# Sht2-V12P0_reg.net
KiCad netlist of a schematic drawn in Altium Designer
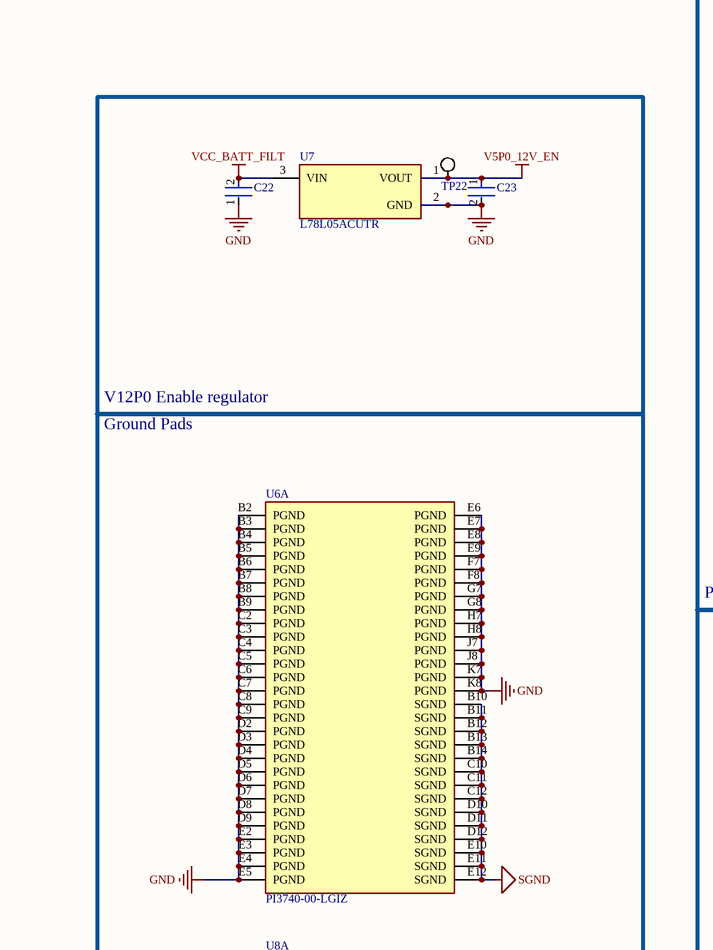
[diagram p0: Sht2-V12P0_reg.SchDoc, top left]
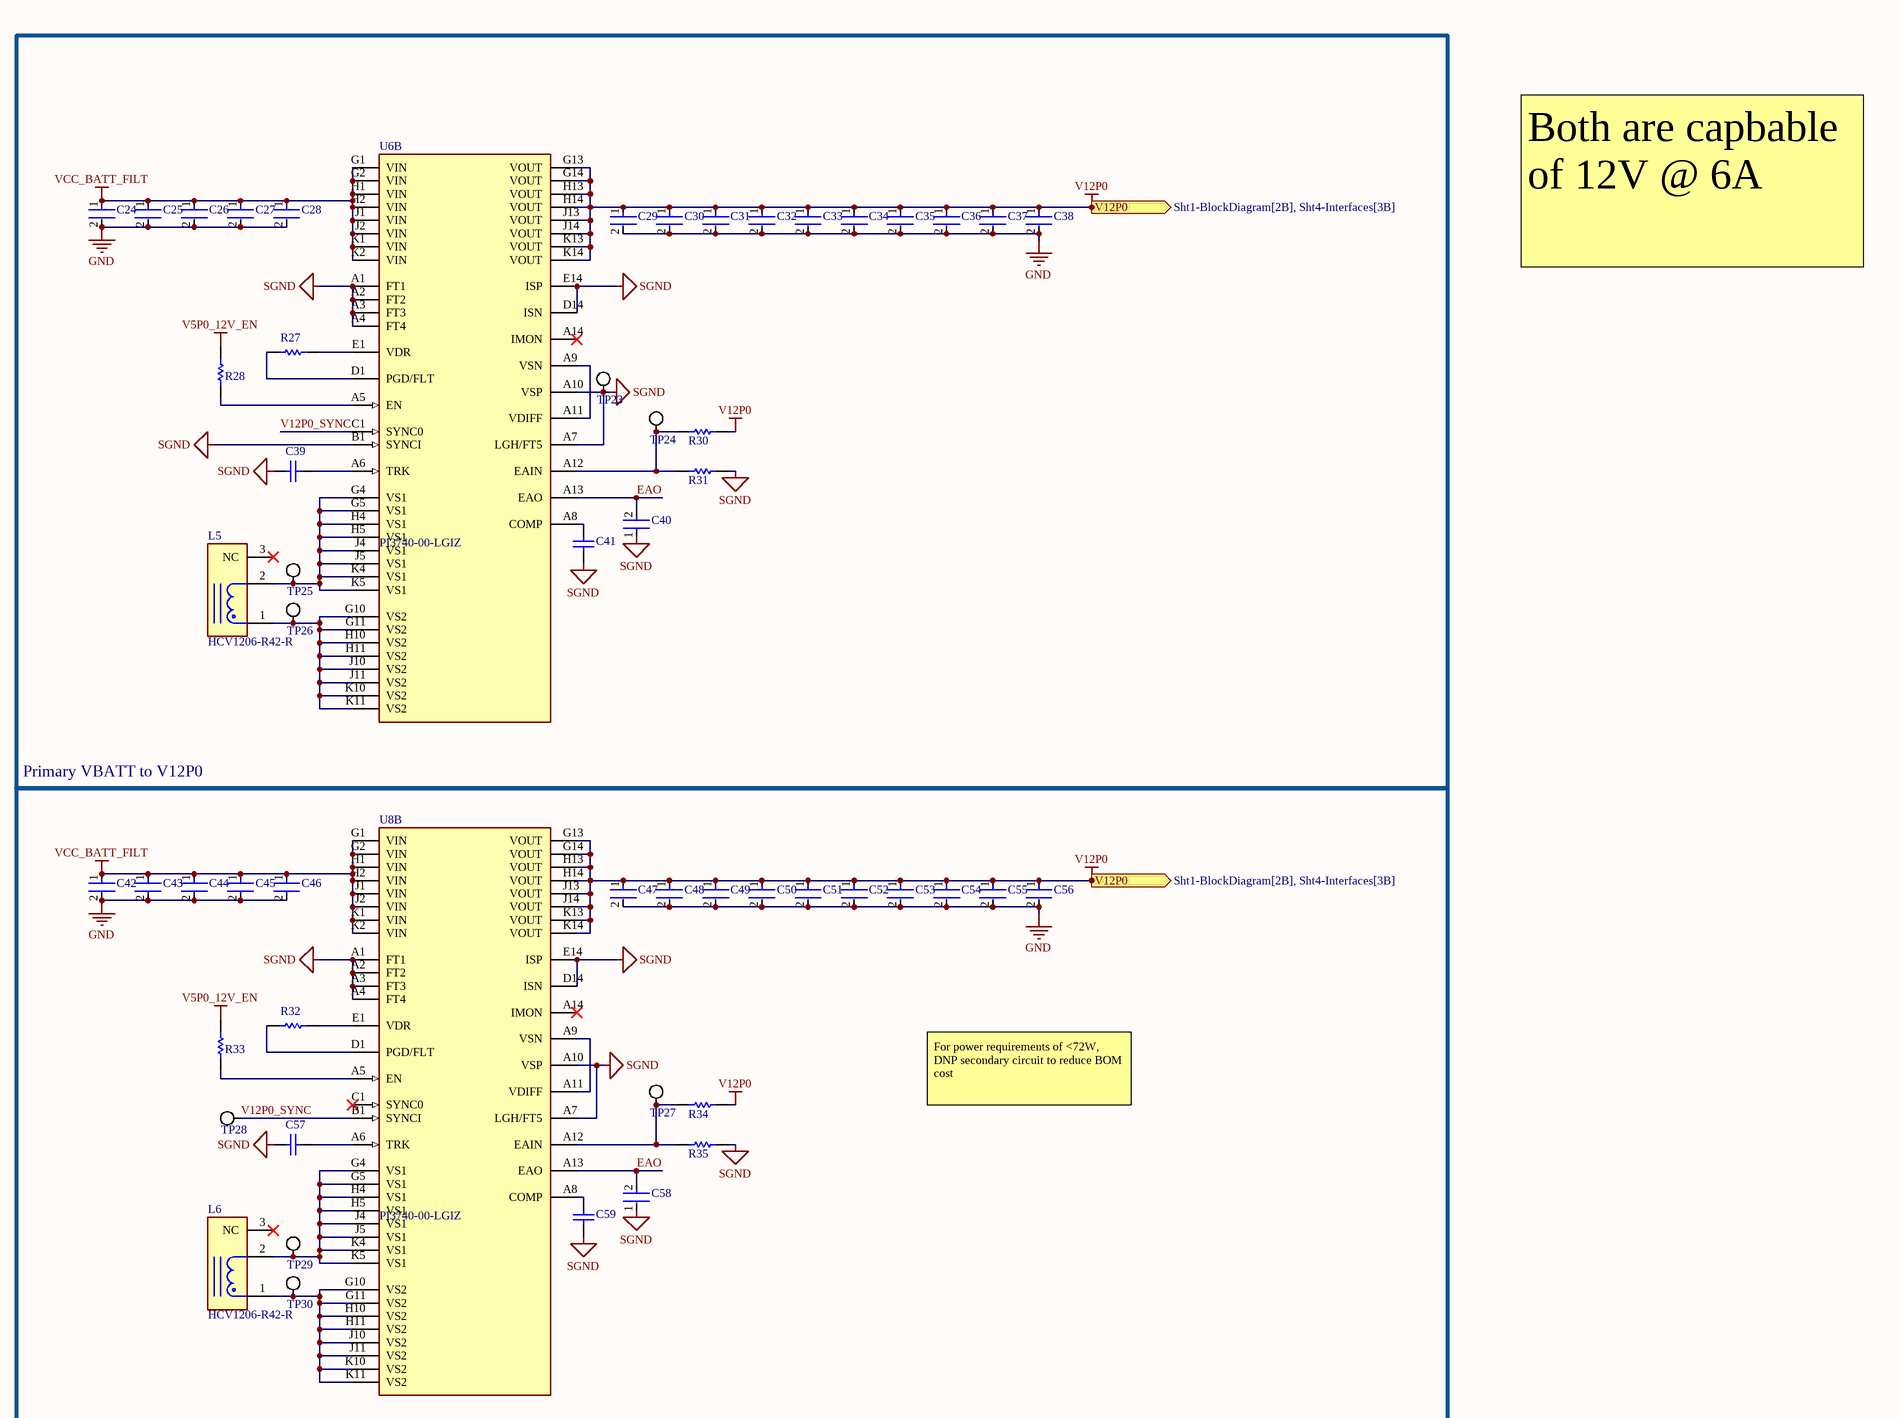
[diagram p1: Sht2-V12P0_reg.SchDoc, top right]
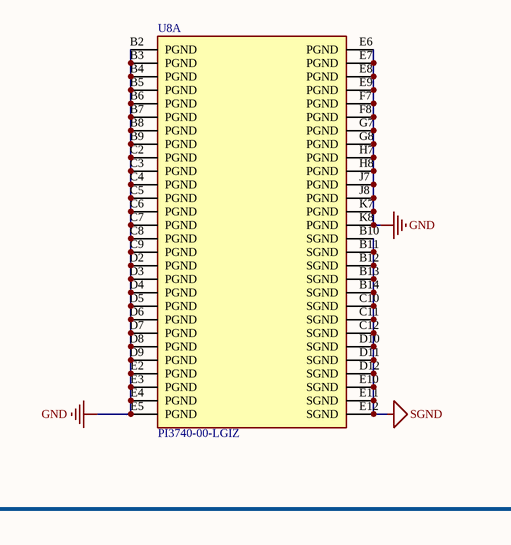
[diagram p2: Sht2-V12P0_reg.SchDoc, bottom left]
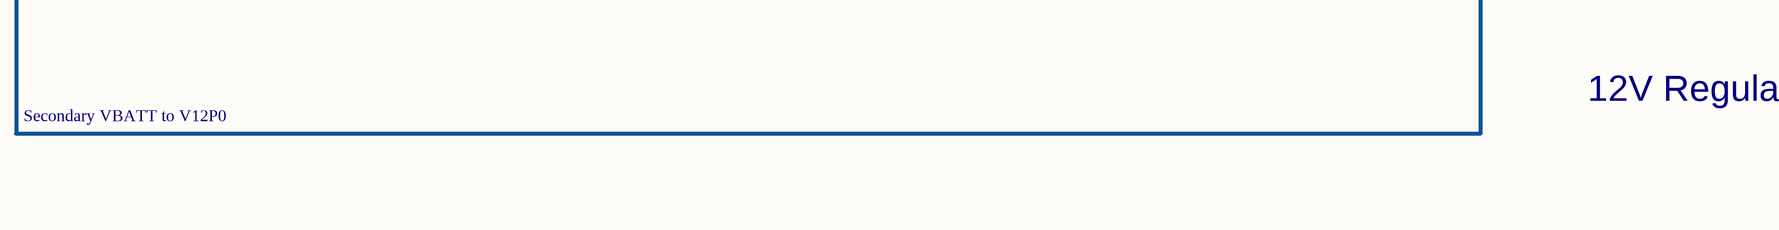
[diagram p3: Sht2-V12P0_reg.SchDoc, bottom right]

(export (version "E")
  (design (tool "Eeschema 10.0.6"))
  (components
    (comp (ref "C22")
      (value "C1608X7R1H334K080AC")
      (footprint "FP-C1608-080-0_1-IPC_A")
      (description "Multilayer Ceramic Capacitors 330nF ±10% 50V X7R SMD 0603")
      (fields (field (name "TOLERANCE") "10%") (field (name "VOLTAGE") "50V"))
      (libsource (lib "Altium Content Vault") (part "236180d848d6139a670b325ea6854c9"))
    )
    (comp (ref "C23")
      (value "CGA3E2X7R1H104K080AA")
      (footprint "FP-CGA3E-0_3-0_1-IPC_A")
      (description "Cap Ceramic 100nF 50V X7R 10% Pad SMD 0603 +125°C Automotive T/R")
      (fields (field (name "TOLERANCE") "10%") (field (name "VOLTAGE") "50V"))
      (libsource (lib "Altium Content Vault") (part "b4654b650e69147ec39a6b967a45e02"))
    )
    (comp (ref "C24")
      (value "12101C225KAT2A")
      (footprint "FP-1210-L_3_3_0_4-W_2_5_0-IPC_B")
      (description "General Purpose Ceramic Capacitor, 1210, 2.2uF, 10%, X7R, 15%, 100V")
      (fields (field (name "TOLERANCE") "10%") (field (name "VOLTAGE") "100V"))
      (libsource (lib "Altium Content Vault") (part "b4654b650e69147ec39a6b967a45e02"))
    )
    (comp (ref "C25")
      (value "12101C225KAT2A")
      (footprint "FP-1210-L_3_3_0_4-W_2_5_0-IPC_B")
      (description "General Purpose Ceramic Capacitor, 1210, 2.2uF, 10%, X7R, 15%, 100V")
      (fields (field (name "TOLERANCE") "10%") (field (name "VOLTAGE") "100V"))
      (libsource (lib "Altium Content Vault") (part "b4654b650e69147ec39a6b967a45e02"))
    )
    (comp (ref "C26")
      (value "12101C225KAT2A")
      (footprint "FP-1210-L_3_3_0_4-W_2_5_0-IPC_B")
      (description "General Purpose Ceramic Capacitor, 1210, 2.2uF, 10%, X7R, 15%, 100V")
      (fields (field (name "TOLERANCE") "10%") (field (name "VOLTAGE") "100V"))
      (libsource (lib "Altium Content Vault") (part "b4654b650e69147ec39a6b967a45e02"))
    )
    (comp (ref "C27")
      (value "12101C225KAT2A")
      (footprint "FP-1210-L_3_3_0_4-W_2_5_0-IPC_B")
      (description "General Purpose Ceramic Capacitor, 1210, 2.2uF, 10%, X7R, 15%, 100V")
      (fields (field (name "TOLERANCE") "10%") (field (name "VOLTAGE") "100V"))
      (libsource (lib "Altium Content Vault") (part "b4654b650e69147ec39a6b967a45e02"))
    )
    (comp (ref "C28")
      (value "12101C225KAT2A")
      (footprint "FP-1210-L_3_3_0_4-W_2_5_0-IPC_B")
      (description "General Purpose Ceramic Capacitor, 1210, 2.2uF, 10%, X7R, 15%, 100V")
      (fields (field (name "TOLERANCE") "10%") (field (name "VOLTAGE") "100V"))
      (libsource (lib "Altium Content Vault") (part "b4654b650e69147ec39a6b967a45e02"))
    )
    (comp (ref "C29")
      (value "GRM32ER71H106KA12L")
      (footprint "FP-GRM32-MFG")
      (description "CAP CER 10UF 50V X7R 1210")
      (fields (field (name "TOLERANCE") "10%") (field (name "MANUFACTURER") "Murata"))
      (libsource (lib "Altium Content Vault") (part "11868f565c42a9108669ba33697ecf6"))
    )
    (comp (ref "C30")
      (value "GRM32ER71H106KA12L")
      (footprint "FP-GRM32-MFG")
      (description "CAP CER 10UF 50V X7R 1210")
      (fields (field (name "TOLERANCE") "10%") (field (name "MANUFACTURER") "Murata"))
      (libsource (lib "Altium Content Vault") (part "11868f565c42a9108669ba33697ecf6"))
    )
    (comp (ref "C31")
      (value "GRM32ER71H106KA12L")
      (footprint "FP-GRM32-MFG")
      (description "CAP CER 10UF 50V X7R 1210")
      (fields (field (name "TOLERANCE") "10%") (field (name "MANUFACTURER") "Murata"))
      (libsource (lib "Altium Content Vault") (part "11868f565c42a9108669ba33697ecf6"))
    )
    (comp (ref "C32")
      (value "GRM32ER71H106KA12L")
      (footprint "FP-GRM32-MFG")
      (description "CAP CER 10UF 50V X7R 1210")
      (fields (field (name "TOLERANCE") "10%") (field (name "MANUFACTURER") "Murata"))
      (libsource (lib "Altium Content Vault") (part "11868f565c42a9108669ba33697ecf6"))
    )
    (comp (ref "C33")
      (value "GRM32ER71H106KA12L")
      (footprint "FP-GRM32-MFG")
      (description "CAP CER 10UF 50V X7R 1210")
      (fields (field (name "TOLERANCE") "10%") (field (name "MANUFACTURER") "Murata"))
      (libsource (lib "Altium Content Vault") (part "11868f565c42a9108669ba33697ecf6"))
    )
    (comp (ref "C34")
      (value "GRM32ER71H106KA12L")
      (footprint "FP-GRM32-MFG")
      (description "CAP CER 10UF 50V X7R 1210")
      (fields (field (name "TOLERANCE") "10%") (field (name "MANUFACTURER") "Murata"))
      (libsource (lib "Altium Content Vault") (part "11868f565c42a9108669ba33697ecf6"))
    )
    (comp (ref "C35")
      (value "GRM32ER71H106KA12L")
      (footprint "FP-GRM32-MFG")
      (description "CAP CER 10UF 50V X7R 1210")
      (fields (field (name "TOLERANCE") "10%") (field (name "MANUFACTURER") "Murata"))
      (libsource (lib "Altium Content Vault") (part "11868f565c42a9108669ba33697ecf6"))
    )
    (comp (ref "C36")
      (value "GRM32ER71H106KA12L")
      (footprint "FP-GRM32-MFG")
      (description "CAP CER 10UF 50V X7R 1210")
      (fields (field (name "TOLERANCE") "10%") (field (name "MANUFACTURER") "Murata"))
      (libsource (lib "Altium Content Vault") (part "11868f565c42a9108669ba33697ecf6"))
    )
    (comp (ref "C37")
      (value "GRM32ER71H106KA12L")
      (footprint "FP-GRM32-MFG")
      (description "CAP CER 10UF 50V X7R 1210")
      (fields (field (name "TOLERANCE") "10%") (field (name "MANUFACTURER") "Murata"))
      (libsource (lib "Altium Content Vault") (part "11868f565c42a9108669ba33697ecf6"))
    )
    (comp (ref "C38")
      (value "GRM32ER71H106KA12L")
      (footprint "FP-GRM32-MFG")
      (description "CAP CER 10UF 50V X7R 1210")
      (fields (field (name "TOLERANCE") "10%") (field (name "MANUFACTURER") "Murata"))
      (libsource (lib "Altium Content Vault") (part "11868f565c42a9108669ba33697ecf6"))
    )
    (comp (ref "C39")
      (value "GRM188R71E473KA01D")
      (footprint "CAPC1608X90X35LL10T15")
      (description "47nF 0603")
      (fields (field (name "MANUFACTURER") "Murata"))
      (libsource (lib "Altium Content Vault") (part "CAP"))
    )
    (comp (ref "C40")
      (value "C1608C0G1H560J080AA")
      (footprint "FP-C1608-080-0_1-IPC_C")
      (description "Multilayer Ceramic Capacitors 56pF ±5% 50V C0G SMD 0603")
      (fields (field (name "TOLERANCE") "5%"))
      (libsource (lib "Altium Content Vault") (part "236180d848d6139a670b325ea6854c9"))
    )
    (comp (ref "C41")
      (value "GRM188R72A472KA01D")
      (footprint "CAPC1608X90X35ML10T15")
      (description "4700pF 0603")
      (fields (field (name "MANUFACTURER") "Murata"))
      (libsource (lib "Altium Content Vault") (part "CAP"))
    )
    (comp (ref "C42")
      (value "12101C225KAT2A")
      (footprint "FP-1210-L_3_3_0_4-W_2_5_0-IPC_B")
      (description "General Purpose Ceramic Capacitor, 1210, 2.2uF, 10%, X7R, 15%, 100V")
      (fields (field (name "TOLERANCE") "10%") (field (name "VOLTAGE") "100V"))
      (libsource (lib "Altium Content Vault") (part "b4654b650e69147ec39a6b967a45e02"))
    )
    (comp (ref "C43")
      (value "12101C225KAT2A")
      (footprint "FP-1210-L_3_3_0_4-W_2_5_0-IPC_B")
      (description "General Purpose Ceramic Capacitor, 1210, 2.2uF, 10%, X7R, 15%, 100V")
      (fields (field (name "TOLERANCE") "10%") (field (name "VOLTAGE") "100V"))
      (libsource (lib "Altium Content Vault") (part "b4654b650e69147ec39a6b967a45e02"))
    )
    (comp (ref "C44")
      (value "12101C225KAT2A")
      (footprint "FP-1210-L_3_3_0_4-W_2_5_0-IPC_B")
      (description "General Purpose Ceramic Capacitor, 1210, 2.2uF, 10%, X7R, 15%, 100V")
      (fields (field (name "TOLERANCE") "10%") (field (name "VOLTAGE") "100V"))
      (libsource (lib "Altium Content Vault") (part "b4654b650e69147ec39a6b967a45e02"))
    )
    (comp (ref "C45")
      (value "12101C225KAT2A")
      (footprint "FP-1210-L_3_3_0_4-W_2_5_0-IPC_B")
      (description "General Purpose Ceramic Capacitor, 1210, 2.2uF, 10%, X7R, 15%, 100V")
      (fields (field (name "TOLERANCE") "10%") (field (name "VOLTAGE") "100V"))
      (libsource (lib "Altium Content Vault") (part "b4654b650e69147ec39a6b967a45e02"))
    )
    (comp (ref "C46")
      (value "12101C225KAT2A")
      (footprint "FP-1210-L_3_3_0_4-W_2_5_0-IPC_B")
      (description "General Purpose Ceramic Capacitor, 1210, 2.2uF, 10%, X7R, 15%, 100V")
      (fields (field (name "TOLERANCE") "10%") (field (name "VOLTAGE") "100V"))
      (libsource (lib "Altium Content Vault") (part "b4654b650e69147ec39a6b967a45e02"))
    )
    (comp (ref "C47")
      (value "GRM32ER71H106KA12L")
      (footprint "FP-GRM32-MFG")
      (description "CAP CER 10UF 50V X7R 1210")
      (fields (field (name "TOLERANCE") "10%") (field (name "MANUFACTURER") "Murata"))
      (libsource (lib "Altium Content Vault") (part "11868f565c42a9108669ba33697ecf6"))
    )
    (comp (ref "C48")
      (value "GRM32ER71H106KA12L")
      (footprint "FP-GRM32-MFG")
      (description "CAP CER 10UF 50V X7R 1210")
      (fields (field (name "TOLERANCE") "10%") (field (name "MANUFACTURER") "Murata"))
      (libsource (lib "Altium Content Vault") (part "11868f565c42a9108669ba33697ecf6"))
    )
    (comp (ref "C49")
      (value "GRM32ER71H106KA12L")
      (footprint "FP-GRM32-MFG")
      (description "CAP CER 10UF 50V X7R 1210")
      (fields (field (name "TOLERANCE") "10%") (field (name "MANUFACTURER") "Murata"))
      (libsource (lib "Altium Content Vault") (part "11868f565c42a9108669ba33697ecf6"))
    )
    (comp (ref "C50")
      (value "GRM32ER71H106KA12L")
      (footprint "FP-GRM32-MFG")
      (description "CAP CER 10UF 50V X7R 1210")
      (fields (field (name "TOLERANCE") "10%") (field (name "MANUFACTURER") "Murata"))
      (libsource (lib "Altium Content Vault") (part "11868f565c42a9108669ba33697ecf6"))
    )
    (comp (ref "C51")
      (value "GRM32ER71H106KA12L")
      (footprint "FP-GRM32-MFG")
      (description "CAP CER 10UF 50V X7R 1210")
      (fields (field (name "TOLERANCE") "10%") (field (name "MANUFACTURER") "Murata"))
      (libsource (lib "Altium Content Vault") (part "11868f565c42a9108669ba33697ecf6"))
    )
    (comp (ref "C52")
      (value "GRM32ER71H106KA12L")
      (footprint "FP-GRM32-MFG")
      (description "CAP CER 10UF 50V X7R 1210")
      (fields (field (name "TOLERANCE") "10%") (field (name "MANUFACTURER") "Murata"))
      (libsource (lib "Altium Content Vault") (part "11868f565c42a9108669ba33697ecf6"))
    )
    (comp (ref "C53")
      (value "GRM32ER71H106KA12L")
      (footprint "FP-GRM32-MFG")
      (description "CAP CER 10UF 50V X7R 1210")
      (fields (field (name "TOLERANCE") "10%") (field (name "MANUFACTURER") "Murata"))
      (libsource (lib "Altium Content Vault") (part "11868f565c42a9108669ba33697ecf6"))
    )
    (comp (ref "C54")
      (value "GRM32ER71H106KA12L")
      (footprint "FP-GRM32-MFG")
      (description "CAP CER 10UF 50V X7R 1210")
      (fields (field (name "TOLERANCE") "10%") (field (name "MANUFACTURER") "Murata"))
      (libsource (lib "Altium Content Vault") (part "11868f565c42a9108669ba33697ecf6"))
    )
    (comp (ref "C55")
      (value "GRM32ER71H106KA12L")
      (footprint "FP-GRM32-MFG")
      (description "CAP CER 10UF 50V X7R 1210")
      (fields (field (name "TOLERANCE") "10%") (field (name "MANUFACTURER") "Murata"))
      (libsource (lib "Altium Content Vault") (part "11868f565c42a9108669ba33697ecf6"))
    )
    (comp (ref "C56")
      (value "GRM32ER71H106KA12L")
      (footprint "FP-GRM32-MFG")
      (description "CAP CER 10UF 50V X7R 1210")
      (fields (field (name "TOLERANCE") "10%") (field (name "MANUFACTURER") "Murata"))
      (libsource (lib "Altium Content Vault") (part "11868f565c42a9108669ba33697ecf6"))
    )
    (comp (ref "C57")
      (value "GRM188R71E473KA01D")
      (footprint "CAPC1608X90X35LL10T15")
      (description "47nF 0603")
      (fields (field (name "MANUFACTURER") "Murata"))
      (libsource (lib "Altium Content Vault") (part "CAP"))
    )
    (comp (ref "C58")
      (value "C1608C0G1H560J080AA")
      (footprint "FP-C1608-080-0_1-IPC_C")
      (description "Multilayer Ceramic Capacitors 56pF ±5% 50V C0G SMD 0603")
      (fields (field (name "TOLERANCE") "5%"))
      (libsource (lib "Altium Content Vault") (part "236180d848d6139a670b325ea6854c9"))
    )
    (comp (ref "C59")
      (value "GRM188R72A472KA01D")
      (footprint "CAPC1608X90X35ML10T15")
      (description "4700pF 0603")
      (fields (field (name "MANUFACTURER") "Murata"))
      (libsource (lib "Altium Content Vault") (part "CAP"))
    )
    (comp (ref "L5")
      (value "HCV1206-R42-R")
      (footprint "FP-HCV1206-R42-R-MFG")
      (description "FIXED IND 420NH 16A 3.15 MOHM")
      (fields (field (name "TOLERANCE") "10%"))
      (libsource (lib "Altium Content Vault") (part "37f71924ba6560a669f32c2ee7c419d"))
    )
    (comp (ref "L6")
      (value "HCV1206-R42-R")
      (footprint "FP-HCV1206-R42-R-MFG")
      (description "FIXED IND 420NH 16A 3.15 MOHM")
      (fields (field (name "TOLERANCE") "10%"))
      (libsource (lib "Altium Content Vault") (part "37f71924ba6560a669f32c2ee7c419d"))
    )
    (comp (ref "R27")
      (value "CRCW060310K0FKEA")
      (footprint "RESC1609X50X30NL8T20")
      (description "Chip Resistor, 10 KOhm, +/- 1%, 100 mW, -55 to 155 degC, 0603 (1608 Metric), RoHS, Tape and Reel")
      (fields (field (name "MANUFACTURER") "Vishay Semiconductor"))
      (libsource (lib "Altium Content Vault") (part "RES-2"))
    )
    (comp (ref "R28")
      (value "CRCW060310K0FKEA")
      (footprint "RESC1609X50X30NL8T20")
      (description "Chip Resistor, 10 KOhm, +/- 1%, 100 mW, -55 to 155 degC, 0603 (1608 Metric), RoHS, Tape and Reel")
      (fields (field (name "MANUFACTURER") "Vishay Semiconductor"))
      (libsource (lib "Altium Content Vault") (part "RES-2"))
    )
    (comp (ref "R30")
      (value "CRCW060310K0FKEA")
      (footprint "RESC1609X50X30NL8T20")
      (description "Chip Resistor, 10 KOhm, +/- 1%, 100 mW, -55 to 155 degC, 0603 (1608 Metric), RoHS, Tape and Reel")
      (fields (field (name "MANUFACTURER") "Vishay Semiconductor"))
      (libsource (lib "Altium Content Vault") (part "RES-2"))
    )
    (comp (ref "R31")
      (value "RC0603FR-071K65L")
      (footprint "RESC1608X55X25ML10T15")
      (description "1.65k 0603")
      (fields (field (name "MANUFACTURER") "Yageo"))
      (libsource (lib "Altium Content Vault") (part "RES"))
    )
    (comp (ref "R32")
      (value "CRCW060310K0FKEA")
      (footprint "RESC1609X50X30NL8T20")
      (description "Chip Resistor, 10 KOhm, +/- 1%, 100 mW, -55 to 155 degC, 0603 (1608 Metric), RoHS, Tape and Reel")
      (fields (field (name "MANUFACTURER") "Vishay Semiconductor"))
      (libsource (lib "Altium Content Vault") (part "RES-2"))
    )
    (comp (ref "R33")
      (value "CRCW060310K0FKEA")
      (footprint "RESC1609X50X30NL8T20")
      (description "Chip Resistor, 10 KOhm, +/- 1%, 100 mW, -55 to 155 degC, 0603 (1608 Metric), RoHS, Tape and Reel")
      (fields (field (name "MANUFACTURER") "Vishay Semiconductor"))
      (libsource (lib "Altium Content Vault") (part "RES-2"))
    )
    (comp (ref "R34")
      (value "CRCW060310K0FKEA")
      (footprint "RESC1609X50X30NL8T20")
      (description "Chip Resistor, 10 KOhm, +/- 1%, 100 mW, -55 to 155 degC, 0603 (1608 Metric), RoHS, Tape and Reel")
      (fields (field (name "MANUFACTURER") "Vishay Semiconductor"))
      (libsource (lib "Altium Content Vault") (part "RES-2"))
    )
    (comp (ref "R35")
      (value "RC0603FR-071K65L")
      (footprint "RESC1608X55X25ML10T15")
      (description "1.65k 0603")
      (fields (field (name "MANUFACTURER") "Yageo"))
      (libsource (lib "Altium Content Vault") (part "RES"))
    )
    (comp (ref "TP22")
      (value "Test Point Pad")
      (footprint "Test Point Pad")
      (description "Test point, Pad, 28 mil")
      (libsource (lib "CMR_PCB_Components") (part "Test Point Pad"))
    )
    (comp (ref "TP23")
      (value "Test Point Pad")
      (footprint "Test Point Pad")
      (description "Test point, Pad, 28 mil")
      (libsource (lib "CMR_PCB_Components") (part "Test Point Pad"))
    )
    (comp (ref "TP24")
      (value "Test Point Pad")
      (footprint "Test Point Pad")
      (description "Test point, Pad, 28 mil")
      (libsource (lib "CMR_PCB_Components") (part "Test Point Pad"))
    )
    (comp (ref "TP25")
      (value "Test Point Pad")
      (footprint "Test Point Pad")
      (description "Test point, Pad, 28 mil")
      (libsource (lib "CMR_PCB_Components") (part "Test Point Pad"))
    )
    (comp (ref "TP26")
      (value "Test Point Pad")
      (footprint "Test Point Pad")
      (description "Test point, Pad, 28 mil")
      (libsource (lib "CMR_PCB_Components") (part "Test Point Pad"))
    )
    (comp (ref "TP27")
      (value "Test Point Pad")
      (footprint "Test Point Pad")
      (description "Test point, Pad, 28 mil")
      (libsource (lib "CMR_PCB_Components") (part "Test Point Pad"))
    )
    (comp (ref "TP28")
      (value "Test Point Pad")
      (footprint "Test Point Pad")
      (description "Test point, Pad, 28 mil")
      (libsource (lib "CMR_PCB_Components") (part "Test Point Pad"))
    )
    (comp (ref "TP29")
      (value "Test Point Pad")
      (footprint "Test Point Pad")
      (description "Test point, Pad, 28 mil")
      (libsource (lib "CMR_PCB_Components") (part "Test Point Pad"))
    )
    (comp (ref "TP30")
      (value "Test Point Pad")
      (footprint "Test Point Pad")
      (description "Test point, Pad, 28 mil")
      (libsource (lib "CMR_PCB_Components") (part "Test Point Pad"))
    )
    (comp (ref "U6")
      (value "PI3740-00-LGIZ")
      (footprint "FP-PI3740-00-LGIZ-MFG")
      (description "DC DC CONVERTER 10-50V")
      (libsource (lib "Altium Content Vault") (part "1066ae71189b305fd66a514a457717d"))
    )
    (comp (ref "U7")
      (value "L78L05ACUTR")
      (footprint "FP-SOT-89-7098166-MFG")
      (description "IC REG LINEAR 5V 100MA SOT89-3")
      (libsource (lib "Altium Content Vault") (part "ae6bee9076d4e2dbe8e374331bf90c1"))
    )
    (comp (ref "U8")
      (value "PI3740-00-LGIZ")
      (footprint "FP-PI3740-00-LGIZ-MFG")
      (description "DC DC CONVERTER 10-50V")
      (libsource (lib "Altium Content Vault") (part "1066ae71189b305fd66a514a457717d"))
    )
  )
  (nets
    (net (code "1") (name "/EAO") (class "Default")
      (node (ref "C40") (pin "2") (pinfunction "2_2") (pintype "passive"))
      (node (ref "C58") (pin "2") (pinfunction "2_2") (pintype "passive"))
      (node (ref "U6") (pin "A13") (pinfunction "EAO_A13") (pintype "passive"))
      (node (ref "U8") (pin "A13") (pinfunction "EAO_A13") (pintype "passive"))
    )
    (net (code "2") (name "/V12P0_SYNC") (class "Default")
      (node (ref "TP28") (pin "1") (pinfunction "1_1") (pintype "passive"))
      (node (ref "U6") (pin "C1") (pinfunction "SYNC0_C1") (pintype "input"))
      (node (ref "U8") (pin "B1") (pinfunction "SYNCI_B1") (pintype "input"))
    )
    (net (code "3") (name "GND") (class "Default")
      (node (ref "C22") (pin "1") (pinfunction "1_1") (pintype "passive"))
      (node (ref "C23") (pin "2") (pinfunction "2_2") (pintype "passive"))
      (node (ref "C24") (pin "2") (pinfunction "2_2") (pintype "passive"))
      (node (ref "C25") (pin "2") (pinfunction "2_2") (pintype "passive"))
      (node (ref "C26") (pin "2") (pinfunction "2_2") (pintype "passive"))
      (node (ref "C27") (pin "2") (pinfunction "2_2") (pintype "passive"))
      (node (ref "C28") (pin "2") (pinfunction "2_2") (pintype "passive"))
      (node (ref "C29") (pin "2") (pinfunction "2_2") (pintype "passive"))
      (node (ref "C30") (pin "2") (pinfunction "2_2") (pintype "passive"))
      (node (ref "C31") (pin "2") (pinfunction "2_2") (pintype "passive"))
      (node (ref "C32") (pin "2") (pinfunction "2_2") (pintype "passive"))
      (node (ref "C33") (pin "2") (pinfunction "2_2") (pintype "passive"))
      (node (ref "C34") (pin "2") (pinfunction "2_2") (pintype "passive"))
      (node (ref "C35") (pin "2") (pinfunction "2_2") (pintype "passive"))
      (node (ref "C36") (pin "2") (pinfunction "2_2") (pintype "passive"))
      (node (ref "C37") (pin "2") (pinfunction "2_2") (pintype "passive"))
      (node (ref "C38") (pin "2") (pinfunction "2_2") (pintype "passive"))
      (node (ref "C42") (pin "2") (pinfunction "2_2") (pintype "passive"))
      (node (ref "C43") (pin "2") (pinfunction "2_2") (pintype "passive"))
      (node (ref "C44") (pin "2") (pinfunction "2_2") (pintype "passive"))
      (node (ref "C45") (pin "2") (pinfunction "2_2") (pintype "passive"))
      (node (ref "C46") (pin "2") (pinfunction "2_2") (pintype "passive"))
      (node (ref "C47") (pin "2") (pinfunction "2_2") (pintype "passive"))
      (node (ref "C48") (pin "2") (pinfunction "2_2") (pintype "passive"))
      (node (ref "C49") (pin "2") (pinfunction "2_2") (pintype "passive"))
      (node (ref "C50") (pin "2") (pinfunction "2_2") (pintype "passive"))
      (node (ref "C51") (pin "2") (pinfunction "2_2") (pintype "passive"))
      (node (ref "C52") (pin "2") (pinfunction "2_2") (pintype "passive"))
      (node (ref "C53") (pin "2") (pinfunction "2_2") (pintype "passive"))
      (node (ref "C54") (pin "2") (pinfunction "2_2") (pintype "passive"))
      (node (ref "C55") (pin "2") (pinfunction "2_2") (pintype "passive"))
      (node (ref "C56") (pin "2") (pinfunction "2_2") (pintype "passive"))
      (node (ref "U6") (pin "B2") (pinfunction "PGND_B2") (pintype "power_in"))
      (node (ref "U6") (pin "B3") (pinfunction "PGND_B3") (pintype "power_in"))
      (node (ref "U6") (pin "B4") (pinfunction "PGND_B4") (pintype "power_in"))
      (node (ref "U6") (pin "B5") (pinfunction "PGND_B5") (pintype "power_in"))
      (node (ref "U6") (pin "B6") (pinfunction "PGND_B6") (pintype "power_in"))
      (node (ref "U6") (pin "B7") (pinfunction "PGND_B7") (pintype "power_in"))
      (node (ref "U6") (pin "B8") (pinfunction "PGND_B8") (pintype "power_in"))
      (node (ref "U6") (pin "B9") (pinfunction "PGND_B9") (pintype "power_in"))
      (node (ref "U6") (pin "C2") (pinfunction "PGND_C2") (pintype "power_in"))
      (node (ref "U6") (pin "C3") (pinfunction "PGND_C3") (pintype "power_in"))
      (node (ref "U6") (pin "C4") (pinfunction "PGND_C4") (pintype "power_in"))
      (node (ref "U6") (pin "C5") (pinfunction "PGND_C5") (pintype "power_in"))
      (node (ref "U6") (pin "C6") (pinfunction "PGND_C6") (pintype "power_in"))
      (node (ref "U6") (pin "C7") (pinfunction "PGND_C7") (pintype "power_in"))
      (node (ref "U6") (pin "C8") (pinfunction "PGND_C8") (pintype "power_in"))
      (node (ref "U6") (pin "C9") (pinfunction "PGND_C9") (pintype "power_in"))
      (node (ref "U6") (pin "D2") (pinfunction "PGND_D2") (pintype "power_in"))
      (node (ref "U6") (pin "D3") (pinfunction "PGND_D3") (pintype "power_in"))
      (node (ref "U6") (pin "D4") (pinfunction "PGND_D4") (pintype "power_in"))
      (node (ref "U6") (pin "D5") (pinfunction "PGND_D5") (pintype "power_in"))
      (node (ref "U6") (pin "D6") (pinfunction "PGND_D6") (pintype "power_in"))
      (node (ref "U6") (pin "D7") (pinfunction "PGND_D7") (pintype "power_in"))
      (node (ref "U6") (pin "D8") (pinfunction "PGND_D8") (pintype "power_in"))
      (node (ref "U6") (pin "D9") (pinfunction "PGND_D9") (pintype "power_in"))
      (node (ref "U6") (pin "E2") (pinfunction "PGND_E2") (pintype "power_in"))
      (node (ref "U6") (pin "E3") (pinfunction "PGND_E3") (pintype "power_in"))
      (node (ref "U6") (pin "E4") (pinfunction "PGND_E4") (pintype "power_in"))
      (node (ref "U6") (pin "E5") (pinfunction "PGND_E5") (pintype "power_in"))
      (node (ref "U6") (pin "E6") (pinfunction "PGND_E6") (pintype "power_in"))
      (node (ref "U6") (pin "E7") (pinfunction "PGND_E7") (pintype "power_in"))
      (node (ref "U6") (pin "E8") (pinfunction "PGND_E8") (pintype "power_in"))
      (node (ref "U6") (pin "E9") (pinfunction "PGND_E9") (pintype "power_in"))
      (node (ref "U6") (pin "F7") (pinfunction "PGND_F7") (pintype "power_in"))
      (node (ref "U6") (pin "F8") (pinfunction "PGND_F8") (pintype "power_in"))
      (node (ref "U6") (pin "G7") (pinfunction "PGND_G7") (pintype "power_in"))
      (node (ref "U6") (pin "G8") (pinfunction "PGND_G8") (pintype "power_in"))
      (node (ref "U6") (pin "H7") (pinfunction "PGND_H7") (pintype "power_in"))
      (node (ref "U6") (pin "H8") (pinfunction "PGND_H8") (pintype "power_in"))
      (node (ref "U6") (pin "J7") (pinfunction "PGND_J7") (pintype "power_in"))
      (node (ref "U6") (pin "J8") (pinfunction "PGND_J8") (pintype "power_in"))
      (node (ref "U6") (pin "K7") (pinfunction "PGND_K7") (pintype "power_in"))
      (node (ref "U6") (pin "K8") (pinfunction "PGND_K8") (pintype "power_in"))
      (node (ref "U7") (pin "2") (pinfunction "GND_2") (pintype "power_in"))
      (node (ref "U8") (pin "B2") (pinfunction "PGND_B2") (pintype "power_in"))
      (node (ref "U8") (pin "B3") (pinfunction "PGND_B3") (pintype "power_in"))
      (node (ref "U8") (pin "B4") (pinfunction "PGND_B4") (pintype "power_in"))
      (node (ref "U8") (pin "B5") (pinfunction "PGND_B5") (pintype "power_in"))
      (node (ref "U8") (pin "B6") (pinfunction "PGND_B6") (pintype "power_in"))
      (node (ref "U8") (pin "B7") (pinfunction "PGND_B7") (pintype "power_in"))
      (node (ref "U8") (pin "B8") (pinfunction "PGND_B8") (pintype "power_in"))
      (node (ref "U8") (pin "B9") (pinfunction "PGND_B9") (pintype "power_in"))
      (node (ref "U8") (pin "C2") (pinfunction "PGND_C2") (pintype "power_in"))
      (node (ref "U8") (pin "C3") (pinfunction "PGND_C3") (pintype "power_in"))
      (node (ref "U8") (pin "C4") (pinfunction "PGND_C4") (pintype "power_in"))
      (node (ref "U8") (pin "C5") (pinfunction "PGND_C5") (pintype "power_in"))
      (node (ref "U8") (pin "C6") (pinfunction "PGND_C6") (pintype "power_in"))
      (node (ref "U8") (pin "C7") (pinfunction "PGND_C7") (pintype "power_in"))
      (node (ref "U8") (pin "C8") (pinfunction "PGND_C8") (pintype "power_in"))
      (node (ref "U8") (pin "C9") (pinfunction "PGND_C9") (pintype "power_in"))
      (node (ref "U8") (pin "D2") (pinfunction "PGND_D2") (pintype "power_in"))
      (node (ref "U8") (pin "D3") (pinfunction "PGND_D3") (pintype "power_in"))
      (node (ref "U8") (pin "D4") (pinfunction "PGND_D4") (pintype "power_in"))
      (node (ref "U8") (pin "D5") (pinfunction "PGND_D5") (pintype "power_in"))
      (node (ref "U8") (pin "D6") (pinfunction "PGND_D6") (pintype "power_in"))
      (node (ref "U8") (pin "D7") (pinfunction "PGND_D7") (pintype "power_in"))
      (node (ref "U8") (pin "D8") (pinfunction "PGND_D8") (pintype "power_in"))
      (node (ref "U8") (pin "D9") (pinfunction "PGND_D9") (pintype "power_in"))
      (node (ref "U8") (pin "E2") (pinfunction "PGND_E2") (pintype "power_in"))
      (node (ref "U8") (pin "E3") (pinfunction "PGND_E3") (pintype "power_in"))
      (node (ref "U8") (pin "E4") (pinfunction "PGND_E4") (pintype "power_in"))
      (node (ref "U8") (pin "E5") (pinfunction "PGND_E5") (pintype "power_in"))
      (node (ref "U8") (pin "E6") (pinfunction "PGND_E6") (pintype "power_in"))
      (node (ref "U8") (pin "E7") (pinfunction "PGND_E7") (pintype "power_in"))
      (node (ref "U8") (pin "E8") (pinfunction "PGND_E8") (pintype "power_in"))
      (node (ref "U8") (pin "E9") (pinfunction "PGND_E9") (pintype "power_in"))
      (node (ref "U8") (pin "F7") (pinfunction "PGND_F7") (pintype "power_in"))
      (node (ref "U8") (pin "F8") (pinfunction "PGND_F8") (pintype "power_in"))
      (node (ref "U8") (pin "G7") (pinfunction "PGND_G7") (pintype "power_in"))
      (node (ref "U8") (pin "G8") (pinfunction "PGND_G8") (pintype "power_in"))
      (node (ref "U8") (pin "H7") (pinfunction "PGND_H7") (pintype "power_in"))
      (node (ref "U8") (pin "H8") (pinfunction "PGND_H8") (pintype "power_in"))
      (node (ref "U8") (pin "J7") (pinfunction "PGND_J7") (pintype "power_in"))
      (node (ref "U8") (pin "J8") (pinfunction "PGND_J8") (pintype "power_in"))
      (node (ref "U8") (pin "K7") (pinfunction "PGND_K7") (pintype "power_in"))
      (node (ref "U8") (pin "K8") (pinfunction "PGND_K8") (pintype "power_in"))
    )
    (net (code "4") (name "Net-(L5-Pad1)") (class "Default")
      (node (ref "L5") (pin "1") (pinfunction "1_1") (pintype "passive"))
      (node (ref "TP26") (pin "1") (pinfunction "1_1") (pintype "passive"))
      (node (ref "U6") (pin "G10") (pinfunction "VS2_G10") (pintype "passive"))
      (node (ref "U6") (pin "G11") (pinfunction "VS2_G11") (pintype "passive"))
      (node (ref "U6") (pin "H10") (pinfunction "VS2_H10") (pintype "passive"))
      (node (ref "U6") (pin "H11") (pinfunction "VS2_H11") (pintype "passive"))
      (node (ref "U6") (pin "J10") (pinfunction "VS2_J10") (pintype "passive"))
      (node (ref "U6") (pin "J11") (pinfunction "VS2_J11") (pintype "passive"))
      (node (ref "U6") (pin "K10") (pinfunction "VS2_K10") (pintype "passive"))
      (node (ref "U6") (pin "K11") (pinfunction "VS2_K11") (pintype "passive"))
    )
    (net (code "5") (name "Net-(L5-Pad2)") (class "Default")
      (node (ref "L5") (pin "2") (pinfunction "2_2") (pintype "passive"))
      (node (ref "TP25") (pin "1") (pinfunction "1_1") (pintype "passive"))
      (node (ref "U6") (pin "G4") (pinfunction "VS1_G4") (pintype "passive"))
      (node (ref "U6") (pin "G5") (pinfunction "VS1_G5") (pintype "passive"))
      (node (ref "U6") (pin "H4") (pinfunction "VS1_H4") (pintype "passive"))
      (node (ref "U6") (pin "H5") (pinfunction "VS1_H5") (pintype "passive"))
      (node (ref "U6") (pin "J4") (pinfunction "VS1_J4") (pintype "passive"))
      (node (ref "U6") (pin "J5") (pinfunction "VS1_J5") (pintype "passive"))
      (node (ref "U6") (pin "K4") (pinfunction "VS1_K4") (pintype "passive"))
      (node (ref "U6") (pin "K5") (pinfunction "VS1_K5") (pintype "passive"))
    )
    (net (code "6") (name "Net-(L6-Pad1)") (class "Default")
      (node (ref "L6") (pin "1") (pinfunction "1_1") (pintype "passive"))
      (node (ref "TP30") (pin "1") (pinfunction "1_1") (pintype "passive"))
      (node (ref "U8") (pin "G10") (pinfunction "VS2_G10") (pintype "passive"))
      (node (ref "U8") (pin "G11") (pinfunction "VS2_G11") (pintype "passive"))
      (node (ref "U8") (pin "H10") (pinfunction "VS2_H10") (pintype "passive"))
      (node (ref "U8") (pin "H11") (pinfunction "VS2_H11") (pintype "passive"))
      (node (ref "U8") (pin "J10") (pinfunction "VS2_J10") (pintype "passive"))
      (node (ref "U8") (pin "J11") (pinfunction "VS2_J11") (pintype "passive"))
      (node (ref "U8") (pin "K10") (pinfunction "VS2_K10") (pintype "passive"))
      (node (ref "U8") (pin "K11") (pinfunction "VS2_K11") (pintype "passive"))
    )
    (net (code "7") (name "Net-(L6-Pad2)") (class "Default")
      (node (ref "L6") (pin "2") (pinfunction "2_2") (pintype "passive"))
      (node (ref "TP29") (pin "1") (pinfunction "1_1") (pintype "passive"))
      (node (ref "U8") (pin "G4") (pinfunction "VS1_G4") (pintype "passive"))
      (node (ref "U8") (pin "G5") (pinfunction "VS1_G5") (pintype "passive"))
      (node (ref "U8") (pin "H4") (pinfunction "VS1_H4") (pintype "passive"))
      (node (ref "U8") (pin "H5") (pinfunction "VS1_H5") (pintype "passive"))
      (node (ref "U8") (pin "J4") (pinfunction "VS1_J4") (pintype "passive"))
      (node (ref "U8") (pin "J5") (pinfunction "VS1_J5") (pintype "passive"))
      (node (ref "U8") (pin "K4") (pinfunction "VS1_K4") (pintype "passive"))
      (node (ref "U8") (pin "K5") (pinfunction "VS1_K5") (pintype "passive"))
    )
    (net (code "8") (name "Net-(U6B-COMP)") (class "Default")
      (node (ref "C41") (pin "2") (pinfunction "2_2") (pintype "passive"))
      (node (ref "U6") (pin "A8") (pinfunction "COMP_A8") (pintype "passive"))
    )
    (net (code "9") (name "Net-(U6B-EAIN)") (class "Default")
      (node (ref "R30") (pin "2") (pinfunction "2_2") (pintype "passive"))
      (node (ref "R31") (pin "1") (pinfunction "1_1") (pintype "passive"))
      (node (ref "TP24") (pin "1") (pinfunction "1_1") (pintype "passive"))
      (node (ref "U6") (pin "A12") (pinfunction "EAIN_A12") (pintype "tri_state"))
    )
    (net (code "10") (name "Net-(U6B-EN)") (class "Default")
      (node (ref "R28") (pin "2") (pinfunction "2_2") (pintype "passive"))
      (node (ref "U6") (pin "A5") (pinfunction "EN_A5") (pintype "input"))
    )
    (net (code "11") (name "Net-(U6B-PGD{slash}FLT)") (class "Default")
      (node (ref "R27") (pin "2") (pinfunction "2_2") (pintype "passive"))
      (node (ref "U6") (pin "D1") (pinfunction "PGD/FLT_D1") (pintype "power_in"))
    )
    (net (code "12") (name "Net-(U6B-TRK)") (class "Default")
      (node (ref "C39") (pin "2") (pinfunction "2_2") (pintype "passive"))
      (node (ref "U6") (pin "A6") (pinfunction "TRK_A6") (pintype "input"))
    )
    (net (code "13") (name "Net-(U6B-VDIFF)") (class "Default")
      (node (ref "U6") (pin "A11") (pinfunction "VDIFF_A11") (pintype "passive"))
      (node (ref "U6") (pin "A9") (pinfunction "VSN_A9") (pintype "tri_state"))
    )
    (net (code "14") (name "Net-(U6B-VDR)") (class "Default")
      (node (ref "R27") (pin "1") (pinfunction "1_1") (pintype "passive"))
      (node (ref "U6") (pin "E1") (pinfunction "VDR_E1") (pintype "power_in"))
    )
    (net (code "15") (name "Net-(U8B-COMP)") (class "Default")
      (node (ref "C59") (pin "2") (pinfunction "2_2") (pintype "passive"))
      (node (ref "U8") (pin "A8") (pinfunction "COMP_A8") (pintype "passive"))
    )
    (net (code "16") (name "Net-(U8B-EAIN)") (class "Default")
      (node (ref "R34") (pin "2") (pinfunction "2_2") (pintype "passive"))
      (node (ref "R35") (pin "1") (pinfunction "1_1") (pintype "passive"))
      (node (ref "TP27") (pin "1") (pinfunction "1_1") (pintype "passive"))
      (node (ref "U8") (pin "A12") (pinfunction "EAIN_A12") (pintype "tri_state"))
    )
    (net (code "17") (name "Net-(U8B-EN)") (class "Default")
      (node (ref "R33") (pin "2") (pinfunction "2_2") (pintype "passive"))
      (node (ref "U8") (pin "A5") (pinfunction "EN_A5") (pintype "input"))
    )
    (net (code "18") (name "Net-(U8B-PGD{slash}FLT)") (class "Default")
      (node (ref "R32") (pin "2") (pinfunction "2_2") (pintype "passive"))
      (node (ref "U8") (pin "D1") (pinfunction "PGD/FLT_D1") (pintype "power_in"))
    )
    (net (code "19") (name "Net-(U8B-TRK)") (class "Default")
      (node (ref "C57") (pin "2") (pinfunction "2_2") (pintype "passive"))
      (node (ref "U8") (pin "A6") (pinfunction "TRK_A6") (pintype "input"))
    )
    (net (code "20") (name "Net-(U8B-VDIFF)") (class "Default")
      (node (ref "U8") (pin "A11") (pinfunction "VDIFF_A11") (pintype "passive"))
      (node (ref "U8") (pin "A9") (pinfunction "VSN_A9") (pintype "tri_state"))
    )
    (net (code "21") (name "Net-(U8B-VDR)") (class "Default")
      (node (ref "R32") (pin "1") (pinfunction "1_1") (pintype "passive"))
      (node (ref "U8") (pin "E1") (pinfunction "VDR_E1") (pintype "power_in"))
    )
    (net (code "22") (name "SGND") (class "Default")
      (node (ref "C39") (pin "1") (pinfunction "1_1") (pintype "passive"))
      (node (ref "C40") (pin "1") (pinfunction "1_1") (pintype "passive"))
      (node (ref "C41") (pin "1") (pinfunction "1_1") (pintype "passive"))
      (node (ref "C57") (pin "1") (pinfunction "1_1") (pintype "passive"))
      (node (ref "C58") (pin "1") (pinfunction "1_1") (pintype "passive"))
      (node (ref "C59") (pin "1") (pinfunction "1_1") (pintype "passive"))
      (node (ref "R31") (pin "2") (pinfunction "2_2") (pintype "passive"))
      (node (ref "R35") (pin "2") (pinfunction "2_2") (pintype "passive"))
      (node (ref "TP23") (pin "1") (pinfunction "1_1") (pintype "passive"))
      (node (ref "U6") (pin "A1") (pinfunction "FT1_A1") (pintype "passive"))
      (node (ref "U6") (pin "A10") (pinfunction "VSP_A10") (pintype "tri_state"))
      (node (ref "U6") (pin "A2") (pinfunction "FT2_A2") (pintype "passive"))
      (node (ref "U6") (pin "A3") (pinfunction "FT3_A3") (pintype "passive"))
      (node (ref "U6") (pin "A4") (pinfunction "FT4_A4") (pintype "passive"))
      (node (ref "U6") (pin "A7") (pinfunction "LGH/FT5_A7") (pintype "passive"))
      (node (ref "U6") (pin "B1") (pinfunction "SYNCI_B1") (pintype "input"))
      (node (ref "U6") (pin "B10") (pinfunction "SGND_B10") (pintype "power_in"))
      (node (ref "U6") (pin "B11") (pinfunction "SGND_B11") (pintype "power_in"))
      (node (ref "U6") (pin "B12") (pinfunction "SGND_B12") (pintype "power_in"))
      (node (ref "U6") (pin "B13") (pinfunction "SGND_B13") (pintype "power_in"))
      (node (ref "U6") (pin "B14") (pinfunction "SGND_B14") (pintype "power_in"))
      (node (ref "U6") (pin "C10") (pinfunction "SGND_C10") (pintype "power_in"))
      (node (ref "U6") (pin "C11") (pinfunction "SGND_C11") (pintype "power_in"))
      (node (ref "U6") (pin "C12") (pinfunction "SGND_C12") (pintype "power_in"))
      (node (ref "U6") (pin "D10") (pinfunction "SGND_D10") (pintype "power_in"))
      (node (ref "U6") (pin "D11") (pinfunction "SGND_D11") (pintype "power_in"))
      (node (ref "U6") (pin "D12") (pinfunction "SGND_D12") (pintype "power_in"))
      (node (ref "U6") (pin "D14") (pinfunction "ISN_D14") (pintype "tri_state"))
      (node (ref "U6") (pin "E10") (pinfunction "SGND_E10") (pintype "power_in"))
      (node (ref "U6") (pin "E11") (pinfunction "SGND_E11") (pintype "power_in"))
      (node (ref "U6") (pin "E12") (pinfunction "SGND_E12") (pintype "power_in"))
      (node (ref "U6") (pin "E14") (pinfunction "ISP_E14") (pintype "tri_state"))
      (node (ref "U8") (pin "A1") (pinfunction "FT1_A1") (pintype "passive"))
      (node (ref "U8") (pin "A10") (pinfunction "VSP_A10") (pintype "tri_state"))
      (node (ref "U8") (pin "A2") (pinfunction "FT2_A2") (pintype "passive"))
      (node (ref "U8") (pin "A3") (pinfunction "FT3_A3") (pintype "passive"))
      (node (ref "U8") (pin "A4") (pinfunction "FT4_A4") (pintype "passive"))
      (node (ref "U8") (pin "A7") (pinfunction "LGH/FT5_A7") (pintype "passive"))
      (node (ref "U8") (pin "B10") (pinfunction "SGND_B10") (pintype "power_in"))
      (node (ref "U8") (pin "B11") (pinfunction "SGND_B11") (pintype "power_in"))
      (node (ref "U8") (pin "B12") (pinfunction "SGND_B12") (pintype "power_in"))
      (node (ref "U8") (pin "B13") (pinfunction "SGND_B13") (pintype "power_in"))
      (node (ref "U8") (pin "B14") (pinfunction "SGND_B14") (pintype "power_in"))
      (node (ref "U8") (pin "C10") (pinfunction "SGND_C10") (pintype "power_in"))
      (node (ref "U8") (pin "C11") (pinfunction "SGND_C11") (pintype "power_in"))
      (node (ref "U8") (pin "C12") (pinfunction "SGND_C12") (pintype "power_in"))
      (node (ref "U8") (pin "D10") (pinfunction "SGND_D10") (pintype "power_in"))
      (node (ref "U8") (pin "D11") (pinfunction "SGND_D11") (pintype "power_in"))
      (node (ref "U8") (pin "D12") (pinfunction "SGND_D12") (pintype "power_in"))
      (node (ref "U8") (pin "D14") (pinfunction "ISN_D14") (pintype "tri_state"))
      (node (ref "U8") (pin "E10") (pinfunction "SGND_E10") (pintype "power_in"))
      (node (ref "U8") (pin "E11") (pinfunction "SGND_E11") (pintype "power_in"))
      (node (ref "U8") (pin "E12") (pinfunction "SGND_E12") (pintype "power_in"))
      (node (ref "U8") (pin "E14") (pinfunction "ISP_E14") (pintype "tri_state"))
    )
    (net (code "23") (name "V5P0_12V_EN") (class "Default")
      (node (ref "C23") (pin "1") (pinfunction "1_1") (pintype "passive"))
      (node (ref "R28") (pin "1") (pinfunction "1_1") (pintype "passive"))
      (node (ref "R33") (pin "1") (pinfunction "1_1") (pintype "passive"))
      (node (ref "TP22") (pin "1") (pinfunction "1_1") (pintype "passive"))
      (node (ref "U7") (pin "1") (pinfunction "VOUT_1") (pintype "power_in"))
    )
    (net (code "24") (name "V12P0") (class "Default")
      (node (ref "C29") (pin "1") (pinfunction "1_1") (pintype "passive"))
      (node (ref "C30") (pin "1") (pinfunction "1_1") (pintype "passive"))
      (node (ref "C31") (pin "1") (pinfunction "1_1") (pintype "passive"))
      (node (ref "C32") (pin "1") (pinfunction "1_1") (pintype "passive"))
      (node (ref "C33") (pin "1") (pinfunction "1_1") (pintype "passive"))
      (node (ref "C34") (pin "1") (pinfunction "1_1") (pintype "passive"))
      (node (ref "C35") (pin "1") (pinfunction "1_1") (pintype "passive"))
      (node (ref "C36") (pin "1") (pinfunction "1_1") (pintype "passive"))
      (node (ref "C37") (pin "1") (pinfunction "1_1") (pintype "passive"))
      (node (ref "C38") (pin "1") (pinfunction "1_1") (pintype "passive"))
      (node (ref "C47") (pin "1") (pinfunction "1_1") (pintype "passive"))
      (node (ref "C48") (pin "1") (pinfunction "1_1") (pintype "passive"))
      (node (ref "C49") (pin "1") (pinfunction "1_1") (pintype "passive"))
      (node (ref "C50") (pin "1") (pinfunction "1_1") (pintype "passive"))
      (node (ref "C51") (pin "1") (pinfunction "1_1") (pintype "passive"))
      (node (ref "C52") (pin "1") (pinfunction "1_1") (pintype "passive"))
      (node (ref "C53") (pin "1") (pinfunction "1_1") (pintype "passive"))
      (node (ref "C54") (pin "1") (pinfunction "1_1") (pintype "passive"))
      (node (ref "C55") (pin "1") (pinfunction "1_1") (pintype "passive"))
      (node (ref "C56") (pin "1") (pinfunction "1_1") (pintype "passive"))
      (node (ref "R30") (pin "1") (pinfunction "1_1") (pintype "passive"))
      (node (ref "R34") (pin "1") (pinfunction "1_1") (pintype "passive"))
      (node (ref "U6") (pin "G13") (pinfunction "VOUT_G13") (pintype "power_in"))
      (node (ref "U6") (pin "G14") (pinfunction "VOUT_G14") (pintype "power_in"))
      (node (ref "U6") (pin "H13") (pinfunction "VOUT_H13") (pintype "power_in"))
      (node (ref "U6") (pin "H14") (pinfunction "VOUT_H14") (pintype "power_in"))
      (node (ref "U6") (pin "J13") (pinfunction "VOUT_J13") (pintype "power_in"))
      (node (ref "U6") (pin "J14") (pinfunction "VOUT_J14") (pintype "power_in"))
      (node (ref "U6") (pin "K13") (pinfunction "VOUT_K13") (pintype "power_in"))
      (node (ref "U6") (pin "K14") (pinfunction "VOUT_K14") (pintype "power_in"))
      (node (ref "U8") (pin "G13") (pinfunction "VOUT_G13") (pintype "power_in"))
      (node (ref "U8") (pin "G14") (pinfunction "VOUT_G14") (pintype "power_in"))
      (node (ref "U8") (pin "H13") (pinfunction "VOUT_H13") (pintype "power_in"))
      (node (ref "U8") (pin "H14") (pinfunction "VOUT_H14") (pintype "power_in"))
      (node (ref "U8") (pin "J13") (pinfunction "VOUT_J13") (pintype "power_in"))
      (node (ref "U8") (pin "J14") (pinfunction "VOUT_J14") (pintype "power_in"))
      (node (ref "U8") (pin "K13") (pinfunction "VOUT_K13") (pintype "power_in"))
      (node (ref "U8") (pin "K14") (pinfunction "VOUT_K14") (pintype "power_in"))
    )
    (net (code "25") (name "VCC_BATT_FILT") (class "Default")
      (node (ref "C22") (pin "2") (pinfunction "2_2") (pintype "passive"))
      (node (ref "C24") (pin "1") (pinfunction "1_1") (pintype "passive"))
      (node (ref "C25") (pin "1") (pinfunction "1_1") (pintype "passive"))
      (node (ref "C26") (pin "1") (pinfunction "1_1") (pintype "passive"))
      (node (ref "C27") (pin "1") (pinfunction "1_1") (pintype "passive"))
      (node (ref "C28") (pin "1") (pinfunction "1_1") (pintype "passive"))
      (node (ref "C42") (pin "1") (pinfunction "1_1") (pintype "passive"))
      (node (ref "C43") (pin "1") (pinfunction "1_1") (pintype "passive"))
      (node (ref "C44") (pin "1") (pinfunction "1_1") (pintype "passive"))
      (node (ref "C45") (pin "1") (pinfunction "1_1") (pintype "passive"))
      (node (ref "C46") (pin "1") (pinfunction "1_1") (pintype "passive"))
      (node (ref "U6") (pin "G1") (pinfunction "VIN_G1") (pintype "power_in"))
      (node (ref "U6") (pin "G2") (pinfunction "VIN_G2") (pintype "power_in"))
      (node (ref "U6") (pin "H1") (pinfunction "VIN_H1") (pintype "power_in"))
      (node (ref "U6") (pin "H2") (pinfunction "VIN_H2") (pintype "power_in"))
      (node (ref "U6") (pin "J1") (pinfunction "VIN_J1") (pintype "power_in"))
      (node (ref "U6") (pin "J2") (pinfunction "VIN_J2") (pintype "power_in"))
      (node (ref "U6") (pin "K1") (pinfunction "VIN_K1") (pintype "power_in"))
      (node (ref "U6") (pin "K2") (pinfunction "VIN_K2") (pintype "power_in"))
      (node (ref "U7") (pin "3") (pinfunction "VIN_3") (pintype "power_in"))
      (node (ref "U8") (pin "G1") (pinfunction "VIN_G1") (pintype "power_in"))
      (node (ref "U8") (pin "G2") (pinfunction "VIN_G2") (pintype "power_in"))
      (node (ref "U8") (pin "H1") (pinfunction "VIN_H1") (pintype "power_in"))
      (node (ref "U8") (pin "H2") (pinfunction "VIN_H2") (pintype "power_in"))
      (node (ref "U8") (pin "J1") (pinfunction "VIN_J1") (pintype "power_in"))
      (node (ref "U8") (pin "J2") (pinfunction "VIN_J2") (pintype "power_in"))
      (node (ref "U8") (pin "K1") (pinfunction "VIN_K1") (pintype "power_in"))
      (node (ref "U8") (pin "K2") (pinfunction "VIN_K2") (pintype "power_in"))
    )
    (net (code "26") (name "unconnected-(L5-NC-Pad3)") (class "Default")
      (node (ref "L5") (pin "3") (pinfunction "NC_3") (pintype "passive+no_connect"))
    )
    (net (code "27") (name "unconnected-(L6-NC-Pad3)") (class "Default")
      (node (ref "L6") (pin "3") (pinfunction "NC_3") (pintype "passive+no_connect"))
    )
    (net (code "28") (name "unconnected-(U6B-IMON-PadA14)") (class "Default")
      (node (ref "U6") (pin "A14") (pinfunction "IMON_A14") (pintype "passive+no_connect"))
    )
    (net (code "29") (name "unconnected-(U8B-IMON-PadA14)") (class "Default")
      (node (ref "U8") (pin "A14") (pinfunction "IMON_A14") (pintype "passive+no_connect"))
    )
    (net (code "30") (name "unconnected-(U8B-SYNC0-PadC1)") (class "Default")
      (node (ref "U8") (pin "C1") (pinfunction "SYNC0_C1") (pintype "input+no_connect"))
    )
  )
)
